# sensor2.net
KiCad netlist of a schematic drawn in EAGLE
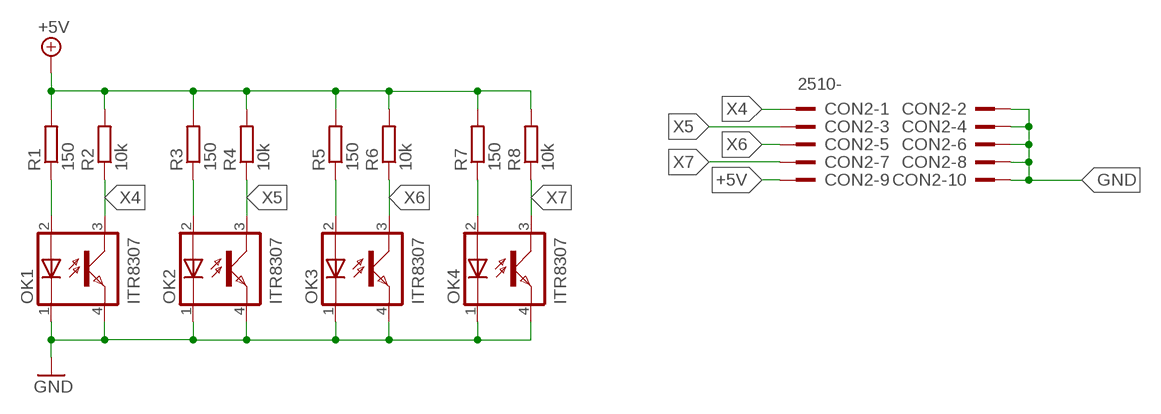
[diagram p0: schematic, sheet 1]

(export (version "E")
  (design (tool "Eeschema 10.0.6"))
  (components
    (comp (ref "CON2")
      (value "2510-")
      (footprint "eagle-import:PAK100_2500-10")
      (fields (field (name "MF") "3M") (field (name "MPN") "2510-6002UB"))
      (libsource (lib "eagle-import") (part "2510-"))
    )
    (comp (ref "OK1")
      (value "ITR8307")
      (footprint "eagle-import:F43")
      (libsource (lib "eagle-import") (part "ITR8307"))
    )
    (comp (ref "OK2")
      (value "ITR8307")
      (footprint "eagle-import:F43")
      (libsource (lib "eagle-import") (part "ITR8307"))
    )
    (comp (ref "OK3")
      (value "ITR8307")
      (footprint "eagle-import:F43")
      (libsource (lib "eagle-import") (part "ITR8307"))
    )
    (comp (ref "OK4")
      (value "ITR8307")
      (footprint "eagle-import:F43")
      (libsource (lib "eagle-import") (part "ITR8307"))
    )
    (comp (ref "R1")
      (value "150")
      (footprint "eagle-import:0204_7")
      (libsource (lib "eagle-import") (part "R-EU_0204/7"))
    )
    (comp (ref "R2")
      (value "10k")
      (footprint "eagle-import:0204_7")
      (libsource (lib "eagle-import") (part "R-EU_0204/7"))
    )
    (comp (ref "R3")
      (value "150")
      (footprint "eagle-import:0204_7")
      (libsource (lib "eagle-import") (part "R-EU_0204/7"))
    )
    (comp (ref "R4")
      (value "10k")
      (footprint "eagle-import:0204_7")
      (libsource (lib "eagle-import") (part "R-EU_0204/7"))
    )
    (comp (ref "R5")
      (value "150")
      (footprint "eagle-import:0204_7")
      (libsource (lib "eagle-import") (part "R-EU_0204/7"))
    )
    (comp (ref "R6")
      (value "10k")
      (footprint "eagle-import:0204_7")
      (libsource (lib "eagle-import") (part "R-EU_0204/7"))
    )
    (comp (ref "R7")
      (value "150")
      (footprint "eagle-import:0204_7")
      (libsource (lib "eagle-import") (part "R-EU_0204/7"))
    )
    (comp (ref "R8")
      (value "10k")
      (footprint "eagle-import:0204_7")
      (libsource (lib "eagle-import") (part "R-EU_0204/7"))
    )
  )
  (nets
    (net (code "1") (name "+5V") (class "Default")
      (node (ref "CON2") (pin "9") (pinfunction "KL_9") (pintype "passive"))
      (node (ref "R1") (pin "2") (pinfunction "2_2") (pintype "passive"))
      (node (ref "R2") (pin "2") (pinfunction "2_2") (pintype "passive"))
      (node (ref "R3") (pin "2") (pinfunction "2_2") (pintype "passive"))
      (node (ref "R4") (pin "2") (pinfunction "2_2") (pintype "passive"))
      (node (ref "R5") (pin "2") (pinfunction "2_2") (pintype "passive"))
      (node (ref "R6") (pin "2") (pinfunction "2_2") (pintype "passive"))
      (node (ref "R7") (pin "2") (pinfunction "2_2") (pintype "passive"))
      (node (ref "R8") (pin "2") (pinfunction "2_2") (pintype "passive"))
    )
    (net (code "2") (name "GND") (class "Default")
      (node (ref "CON2") (pin "10") (pinfunction "KL_10") (pintype "passive"))
      (node (ref "CON2") (pin "2") (pinfunction "KL_2") (pintype "passive"))
      (node (ref "CON2") (pin "4") (pinfunction "KL_4") (pintype "passive"))
      (node (ref "CON2") (pin "6") (pinfunction "KL_6") (pintype "passive"))
      (node (ref "CON2") (pin "8") (pinfunction "KL_8") (pintype "passive"))
      (node (ref "OK1") (pin "1") (pinfunction "C_1") (pintype "passive"))
      (node (ref "OK1") (pin "4") (pinfunction "EMIT_4") (pintype "passive"))
      (node (ref "OK2") (pin "1") (pinfunction "C_1") (pintype "passive"))
      (node (ref "OK2") (pin "4") (pinfunction "EMIT_4") (pintype "passive"))
      (node (ref "OK3") (pin "1") (pinfunction "C_1") (pintype "passive"))
      (node (ref "OK3") (pin "4") (pinfunction "EMIT_4") (pintype "passive"))
      (node (ref "OK4") (pin "1") (pinfunction "C_1") (pintype "passive"))
      (node (ref "OK4") (pin "4") (pinfunction "EMIT_4") (pintype "passive"))
    )
    (net (code "3") (name "Net-(OK1-A)") (class "Default")
      (node (ref "OK1") (pin "2") (pinfunction "A_2") (pintype "passive"))
      (node (ref "R1") (pin "1") (pinfunction "1_1") (pintype "passive"))
    )
    (net (code "4") (name "Net-(OK2-A)") (class "Default")
      (node (ref "OK2") (pin "2") (pinfunction "A_2") (pintype "passive"))
      (node (ref "R3") (pin "1") (pinfunction "1_1") (pintype "passive"))
    )
    (net (code "5") (name "Net-(OK3-A)") (class "Default")
      (node (ref "OK3") (pin "2") (pinfunction "A_2") (pintype "passive"))
      (node (ref "R5") (pin "1") (pinfunction "1_1") (pintype "passive"))
    )
    (net (code "6") (name "Net-(OK4-A)") (class "Default")
      (node (ref "OK4") (pin "2") (pinfunction "A_2") (pintype "passive"))
      (node (ref "R7") (pin "1") (pinfunction "1_1") (pintype "passive"))
    )
    (net (code "7") (name "X4") (class "Default")
      (node (ref "CON2") (pin "1") (pinfunction "KL_1") (pintype "passive"))
      (node (ref "OK1") (pin "3") (pinfunction "COL_3") (pintype "passive"))
      (node (ref "R2") (pin "1") (pinfunction "1_1") (pintype "passive"))
    )
    (net (code "8") (name "X5") (class "Default")
      (node (ref "CON2") (pin "3") (pinfunction "KL_3") (pintype "passive"))
      (node (ref "OK2") (pin "3") (pinfunction "COL_3") (pintype "passive"))
      (node (ref "R4") (pin "1") (pinfunction "1_1") (pintype "passive"))
    )
    (net (code "9") (name "X6") (class "Default")
      (node (ref "CON2") (pin "5") (pinfunction "KL_5") (pintype "passive"))
      (node (ref "OK3") (pin "3") (pinfunction "COL_3") (pintype "passive"))
      (node (ref "R6") (pin "1") (pinfunction "1_1") (pintype "passive"))
    )
    (net (code "10") (name "X7") (class "Default")
      (node (ref "CON2") (pin "7") (pinfunction "KL_7") (pintype "passive"))
      (node (ref "OK4") (pin "3") (pinfunction "COL_3") (pintype "passive"))
      (node (ref "R8") (pin "1") (pinfunction "1_1") (pintype "passive"))
    )
  )
)
